# hub_small.net
KiCad netlist of a schematic drawn in EAGLE
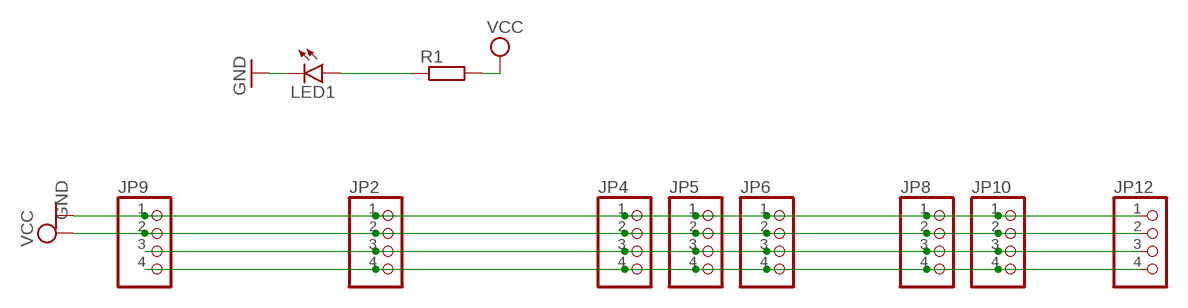
[diagram p0: schematic, sheet 1]

(export (version "E")
  (design (tool "Eeschema 10.0.6"))
  (components
    (comp (ref "JP2")
      (value "PINHD-1X04_2.54-SMD")
      (footprint "eagle-import:1X04SMD")
      (libsource (lib "eagle-import") (part "PINHD-1X04_2.54-SMD"))
    )
    (comp (ref "JP4")
      (value "PINHD-1X04_2.54-SMD")
      (footprint "eagle-import:1X04SMD")
      (libsource (lib "eagle-import") (part "PINHD-1X04_2.54-SMD"))
    )
    (comp (ref "JP5")
      (value "PINHD-1X04_2.54-SMD")
      (footprint "eagle-import:1X04SMD")
      (libsource (lib "eagle-import") (part "PINHD-1X04_2.54-SMD"))
    )
    (comp (ref "JP6")
      (value "PINHD-1X04_2.54-SMD")
      (footprint "eagle-import:1X04SMD")
      (libsource (lib "eagle-import") (part "PINHD-1X04_2.54-SMD"))
    )
    (comp (ref "JP8")
      (value "PINHD-1X04_2.54-SMD")
      (footprint "eagle-import:1X04SMD")
      (libsource (lib "eagle-import") (part "PINHD-1X04_2.54-SMD"))
    )
    (comp (ref "JP9")
      (value "PINHD-1X04_2.54-SMD")
      (footprint "eagle-import:1X04SMD")
      (libsource (lib "eagle-import") (part "PINHD-1X04_2.54-SMD"))
    )
    (comp (ref "JP10")
      (value "PINHD-1X04_2.54-SMD")
      (footprint "eagle-import:1X04SMD")
      (libsource (lib "eagle-import") (part "PINHD-1X04_2.54-SMD"))
    )
    (comp (ref "JP12")
      (value "PINHD-1X04_2.54-SMD")
      (footprint "eagle-import:1X04SMD")
      (libsource (lib "eagle-import") (part "PINHD-1X04_2.54-SMD"))
    )
    (comp (ref "LED1")
      (value "LEDCHIPLED_1206")
      (footprint "eagle-import:CHIPLED_1206")
      (libsource (lib "eagle-import") (part "LEDCHIPLED_1206"))
    )
    (comp (ref "R1")
      (value "R-EU_R1206")
      (footprint "eagle-import:R1206")
      (libsource (lib "eagle-import") (part "R-EU_R1206"))
    )
  )
  (nets
    (net (code "1") (name "GND") (class "Default")
      (node (ref "JP10") (pin "1") (pinfunction "1_1") (pintype "passive"))
      (node (ref "JP12") (pin "1") (pinfunction "1_1") (pintype "passive"))
      (node (ref "JP2") (pin "1") (pinfunction "1_1") (pintype "passive"))
      (node (ref "JP4") (pin "1") (pinfunction "1_1") (pintype "passive"))
      (node (ref "JP5") (pin "1") (pinfunction "1_1") (pintype "passive"))
      (node (ref "JP6") (pin "1") (pinfunction "1_1") (pintype "passive"))
      (node (ref "JP8") (pin "1") (pinfunction "1_1") (pintype "passive"))
      (node (ref "JP9") (pin "1") (pinfunction "1_1") (pintype "passive"))
      (node (ref "LED1") (pin "C") (pinfunction "C_C") (pintype "passive"))
    )
    (net (code "2") (name "Net-(JP10-Pad3)") (class "Default")
      (node (ref "JP10") (pin "3") (pinfunction "3_3") (pintype "passive"))
      (node (ref "JP12") (pin "3") (pinfunction "3_3") (pintype "passive"))
      (node (ref "JP2") (pin "3") (pinfunction "3_3") (pintype "passive"))
      (node (ref "JP4") (pin "3") (pinfunction "3_3") (pintype "passive"))
      (node (ref "JP5") (pin "3") (pinfunction "3_3") (pintype "passive"))
      (node (ref "JP6") (pin "3") (pinfunction "3_3") (pintype "passive"))
      (node (ref "JP8") (pin "3") (pinfunction "3_3") (pintype "passive"))
      (node (ref "JP9") (pin "3") (pinfunction "3_3") (pintype "passive"))
    )
    (net (code "3") (name "Net-(JP10-Pad4)") (class "Default")
      (node (ref "JP10") (pin "4") (pinfunction "4_4") (pintype "passive"))
      (node (ref "JP12") (pin "4") (pinfunction "4_4") (pintype "passive"))
      (node (ref "JP2") (pin "4") (pinfunction "4_4") (pintype "passive"))
      (node (ref "JP4") (pin "4") (pinfunction "4_4") (pintype "passive"))
      (node (ref "JP5") (pin "4") (pinfunction "4_4") (pintype "passive"))
      (node (ref "JP6") (pin "4") (pinfunction "4_4") (pintype "passive"))
      (node (ref "JP8") (pin "4") (pinfunction "4_4") (pintype "passive"))
      (node (ref "JP9") (pin "4") (pinfunction "4_4") (pintype "passive"))
    )
    (net (code "4") (name "Net-(LED1-PadA)") (class "Default")
      (node (ref "LED1") (pin "A") (pinfunction "A_A") (pintype "passive"))
      (node (ref "R1") (pin "1") (pinfunction "1_1") (pintype "passive"))
    )
    (net (code "5") (name "VCC") (class "Default")
      (node (ref "JP10") (pin "2") (pinfunction "2_2") (pintype "passive"))
      (node (ref "JP12") (pin "2") (pinfunction "2_2") (pintype "passive"))
      (node (ref "JP2") (pin "2") (pinfunction "2_2") (pintype "passive"))
      (node (ref "JP4") (pin "2") (pinfunction "2_2") (pintype "passive"))
      (node (ref "JP5") (pin "2") (pinfunction "2_2") (pintype "passive"))
      (node (ref "JP6") (pin "2") (pinfunction "2_2") (pintype "passive"))
      (node (ref "JP8") (pin "2") (pinfunction "2_2") (pintype "passive"))
      (node (ref "JP9") (pin "2") (pinfunction "2_2") (pintype "passive"))
      (node (ref "R1") (pin "2") (pinfunction "2_2") (pintype "passive"))
    )
  )
)
